# A4950.net
KiCad netlist of a schematic drawn in Altium Designer
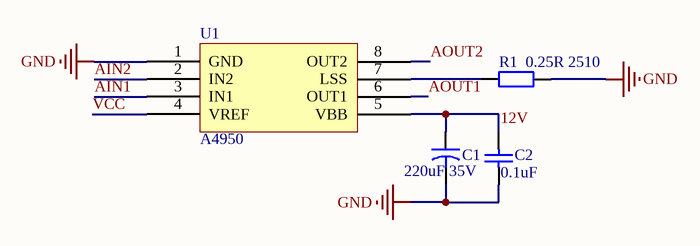
[diagram p0: 电机驱动模块A4950.SchDoc]

(export (version "E")
  (design (tool "Eeschema 10.0.6"))
  (components
    (comp (ref "C1")
      (value "220uF 35V")
      (footprint "CAPR5-4X5")
      (description "Capacitor")
      (fields (field (name "Comment") "Cap2") (field (name "PUBLISHER") "Altium Limited"))
      (libsource (lib "Miscellaneous Devices") (part "Cap2"))
    )
    (comp (ref "C2")
      (value "0.1uF")
      (footprint "RAD-0.3")
      (description "Capacitor")
      (fields (field (name "Comment") "Cap") (field (name "PUBLISHER") "Altium Limited"))
      (libsource (lib "Miscellaneous Devices") (part "Cap"))
    )
    (comp (ref "R1")
      (value "0.25R 2510")
      (footprint "AXIAL-0.4")
      (description "Resistor")
      (fields (field (name "Comment") "Res2") (field (name "PUBLISHER") "Altium Limited"))
      (libsource (lib "Miscellaneous Devices") (part "Res2"))
    )
    (comp (ref "U1") (value "A4950") (libsource (lib "A4950") (part "A4950")))
  )
  (nets
    (net (code "2") (name "/AIN1") (class "Default")
      (node (ref "U1") (pin "3") (pinfunction "IN1_3") (pintype "passive"))
    )
    (net (code "3") (name "/AIN2") (class "Default")
      (node (ref "U1") (pin "2") (pinfunction "IN2_2") (pintype "passive"))
    )
    (net (code "4") (name "/AOUT1") (class "Default")
      (node (ref "U1") (pin "6") (pinfunction "OUT1_6") (pintype "passive"))
    )
    (net (code "5") (name "/AOUT2") (class "Default")
      (node (ref "U1") (pin "8") (pinfunction "OUT2_8") (pintype "passive"))
    )
    (net (code "6") (name "/VCC") (class "Default")
      (node (ref "U1") (pin "4") (pinfunction "VREF_4") (pintype "passive"))
    )
    (net (code "7") (name "GND") (class "Default")
      (node (ref "C1") (pin "2") (pinfunction "2_2") (pintype "passive"))
      (node (ref "C2") (pin "1") (pinfunction "1_1") (pintype "passive"))
      (node (ref "R1") (pin "2") (pinfunction "2_2") (pintype "passive"))
      (node (ref "U1") (pin "1") (pinfunction "GND_1") (pintype "passive"))
    )
    (net (code "8") (name "Net-(U1-LSS)") (class "Default")
      (node (ref "R1") (pin "1") (pinfunction "1_1") (pintype "passive"))
      (node (ref "U1") (pin "7") (pinfunction "LSS_7") (pintype "passive"))
    )
    (net (code "9") (name "Net-(U1-VBB)") (class "Default")
      (node (ref "C1") (pin "1") (pinfunction "1_1") (pintype "passive"))
      (node (ref "C2") (pin "2") (pinfunction "2_2") (pintype "passive"))
      (node (ref "U1") (pin "5") (pinfunction "VBB_5") (pintype "passive"))
    )
  )
)
